# AFE.net
KiCad netlist of a schematic drawn in Altium Designer
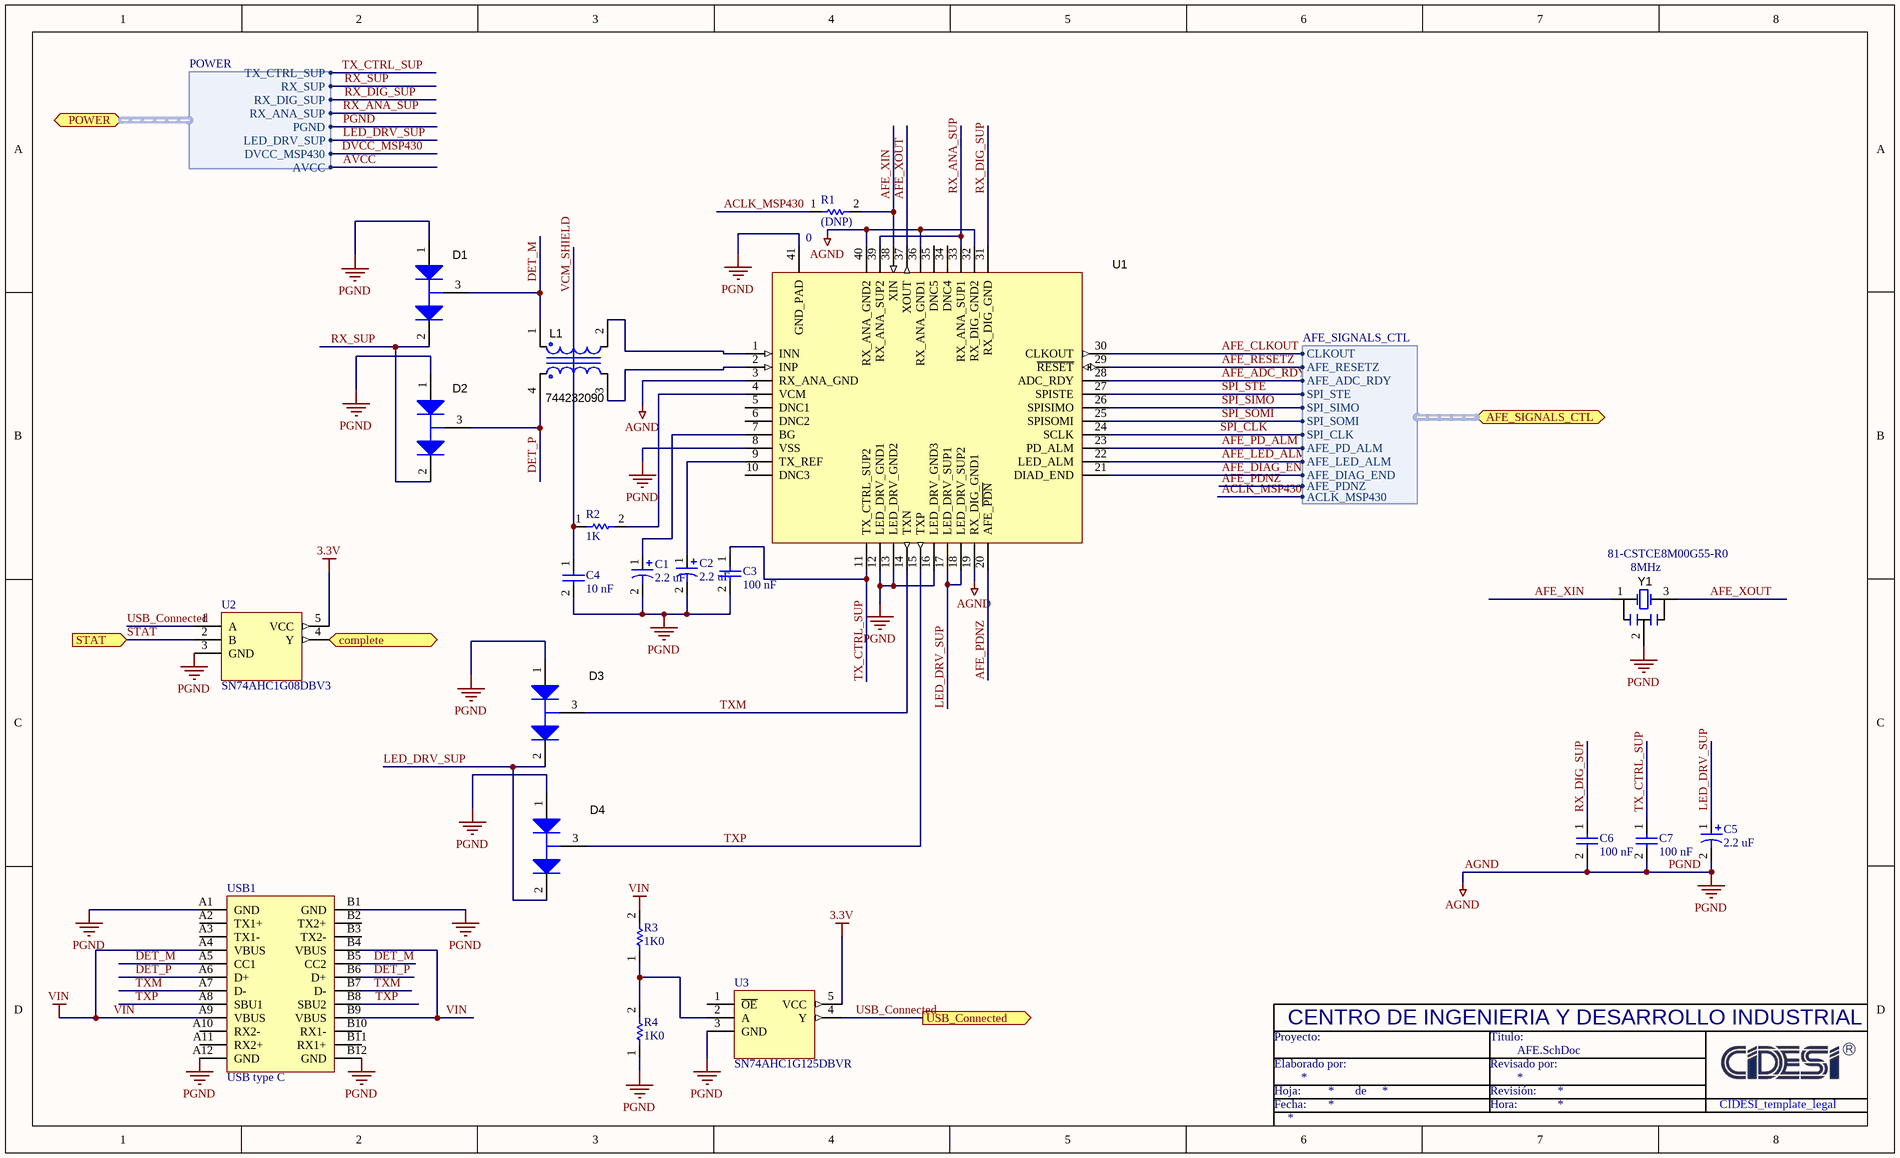
[diagram p0: AFE.SchDoc]

(export (version "E")
  (design (tool "Eeschema 10.0.6"))
  (components
    (comp (ref "C1")
      (value "2.2 uF")
      (footprint "C0603_P")
      (description "NICHICON - F981A225MMA - CAPACITOR TANT, 2.2UF, 10V, SMD 20%")
      (libsource (lib "TarjetaPrincipalV1_4") (part "F981A225MMA"))
    )
    (comp (ref "C2")
      (value "2.2 uF")
      (footprint "C0603_P")
      (description "NICHICON - F981A225MMA - CAPACITOR TANT, 2.2UF, 10V, SMD 20%")
      (libsource (lib "TarjetaPrincipalV1_4") (part "F981A225MMA"))
    )
    (comp (ref "C3")
      (value "100 nF")
      (footprint "C0402")
      (description "TDK - C1005X7R1H104M050BB - CAP CERAMIC, 0.1UF, 50V, X7R, 0402")
      (libsource (lib "TarjetaPrincipalV1_4") (part "C1005X7R1H104M050BB"))
    )
    (comp (ref "C4")
      (value "10 nF")
      (footprint "C0402")
      (description "TDK - C1005X7R1H103K050BB - CAP CERAMIC, 0.01UF, 50V, X7R, 0402")
      (libsource (lib "TarjetaPrincipalV1_4") (part "C1005X7R1H103K050BB"))
    )
    (comp (ref "C5")
      (value "2.2 uF")
      (footprint "C0603_P")
      (description "NICHICON - F981A225MMA - CAPACITOR TANT, 2.2UF, 10V, SMD 20%")
      (libsource (lib "TarjetaPrincipalV1_4") (part "F981A225MMA"))
    )
    (comp (ref "C6")
      (value "100 nF")
      (footprint "C0402")
      (description "TDK - C1005X7R1H104M050BB - CAP CERAMIC, 0.1UF, 50V, X7R, 0402")
      (libsource (lib "TarjetaPrincipalV1_4") (part "C1005X7R1H104M050BB"))
    )
    (comp (ref "C7")
      (value "100 nF")
      (footprint "C0402")
      (description "TDK - C1005X7R1H104M050BB - CAP CERAMIC, 0.1UF, 50V, X7R, 0402")
      (libsource (lib "TarjetaPrincipalV1_4") (part "C1005X7R1H104M050BB"))
    )
    (comp (ref "D1")
      (value "1651159")
      (footprint "SOT-323")
      (description "ON SEMICONDUCTOR - BAV99WT1G - DIODE SMALL SIGNAL, 750MA")
      (fields (field (name "PART NUMBER") "BAV99WT1G") (field (name "MANUFACTURER") "ON SEMICONDUCTOR"))
      (libsource (lib "TarjetaPrincipalV1_4") (part "BAV99WT1G"))
    )
    (comp (ref "D2")
      (value "1651159")
      (footprint "SOT-323")
      (description "ON SEMICONDUCTOR - BAV99WT1G - DIODE SMALL SIGNAL, 750MA")
      (fields (field (name "PART NUMBER") "BAV99WT1G") (field (name "MANUFACTURER") "ON SEMICONDUCTOR"))
      (libsource (lib "TarjetaPrincipalV1_4") (part "BAV99WT1G"))
    )
    (comp (ref "D3")
      (value "1651159")
      (footprint "SOT-323")
      (description "ON SEMICONDUCTOR - BAV99WT1G - DIODE SMALL SIGNAL, 750MA")
      (fields (field (name "PART NUMBER") "BAV99WT1G") (field (name "MANUFACTURER") "ON SEMICONDUCTOR"))
      (libsource (lib "TarjetaPrincipalV1_4") (part "BAV99WT1G"))
    )
    (comp (ref "D4")
      (value "1651159")
      (footprint "SOT-323")
      (description "ON SEMICONDUCTOR - BAV99WT1G - DIODE SMALL SIGNAL, 750MA")
      (fields (field (name "PART NUMBER") "BAV99WT1G") (field (name "MANUFACTURER") "ON SEMICONDUCTOR"))
      (libsource (lib "TarjetaPrincipalV1_4") (part "BAV99WT1G"))
    )
    (comp (ref "L1")
      (value "744232090")
      (footprint "IND_1206-4P")
      (description "WURTH ELEKTRONIK - 744232090 - FILTER, COMMON, EMI, 0.37A")
      (libsource (lib "TarjetaPrincipalV1_4") (part "DLW31SN900SQ2L"))
    )
    (comp (ref "R1")
      (value "(DNP)")
      (footprint "0201")
      (description "VISHAY DALE - CRCW02010000Z0ED - RESISTOR, CHIP, JUMPER, ZERO OHM, 50mW, FULL REEL")
      (fields (field (name "ALTIUM_VALUE") "0"))
      (libsource (lib "TarjetaPrincipalV1_4") (part "CRCW02010000Z0ED"))
    )
    (comp (ref "R2")
      (value "1K")
      (footprint "0201")
      (description "VISHAY DALE - CRCW02011K00FNED - RESISTOR, THICK FILM CHIP, 1KOHM 50mW, 1%, FULL REEL")
      (libsource (lib "TarjetaPrincipalV1_4") (part "CRCW02011K00FNED"))
    )
    (comp (ref "R3")
      (value "CRCW04021K00FKEDC")
      (footprint "R-0402")
      (description "Resistor")
      (fields
        (field (name "MANUFACTURER") "Vishay / Dale")
        (field (name "TOLERANCE") "1 %")
        (field (name "RESISTANCE") "1K0")
      )
      (libsource (lib "TarjetaPrincipalV1_4") (part "CRCW04021K00FKEDC"))
    )
    (comp (ref "R4")
      (value "CRCW04021K00FKEDC")
      (footprint "R-0402")
      (description "Resistor")
      (fields
        (field (name "MANUFACTURER") "Vishay / Dale")
        (field (name "TOLERANCE") "1 %")
        (field (name "RESISTANCE") "1K0")
      )
      (libsource (lib "TarjetaPrincipalV1_4") (part "CRCW04021K00FKEDC"))
    )
    (comp (ref "U1")
      (value "~")
      (footprint "QFN-40[RHA-42P]")
      (description "IC, INTEGRATED ANALOG FRONT-END FOR HEART RATE MONITORS AND LOW-COST PULSE OXIMETERS, QFN-40")
      (fields (field (name "PART NUMBER") "AFE4400") (field (name "MANUFACTURER") "TEXAS INSTRUMENTS"))
      (libsource (lib "TarjetaPrincipalV1_4") (part "AFE4400"))
    )
    (comp (ref "U2")
      (value "~")
      (footprint "SOT23-5")
      (description "AND GATE")
      (fields
        (field (name "MANUFACTURER") "Texas Instruments")
        (field (name "MANUFACTURER PART NUMBER") "SN74AHC1G08DBV3")
      )
      (libsource (lib "TarjetaPrincipalV1_4") (part "SN74AHC1G08DBV3"))
    )
    (comp (ref "U3")
      (value "~")
      (footprint "SOT23-5")
      (description "BUFFER")
      (fields
        (field (name "MANUFACTURER") "Texas Instruments")
        (field (name "MANUFACTURER PART NUMBER") "SN74AHC1G125DBVR")
      )
      (libsource (lib "TarjetaPrincipalV1_4") (part "SN74AHC1G125DBVR"))
    )
    (comp (ref "USB1")
      (value "USB type C")
      (footprint "USB C")
      (libsource (lib "TarjetaPrincipalV1_4") (part "USB C"))
    )
    (comp (ref "Y1")
      (value "8MHz")
      (footprint "RESONATOR-1.3X3.2-MURATA")
      (description "CRYSTAL, PIEZO CERAMIC RESONATOR, 8.00 MHz, SMD, 0.5%, 33pF, SMD")
      (fields
        (field (name "MANUFACTURER") "MURATA")
        (field (name "PART NUMBER") "CSTCE8M00G55-R0")
        (field (name "SUPPLIER PART NUMBER 1") "81-CSTCE8M00G55-R0")
      )
      (libsource (lib "TarjetaPrincipalV1_4") (part "CSTCE8M00G55-R0"))
    )
  )
  (nets
    (net (code "3") (name "/ACLK_MSP430") (class "Default")
      (node (ref "R1") (pin "1") (pinfunction "1_1") (pintype "passive"))
    )
    (net (code "4") (name "/AFE_ADC_RDY") (class "Default")
      (node (ref "U1") (pin "28") (pinfunction "ADC_RDY_28") (pintype "passive"))
    )
    (net (code "5") (name "/AFE_CLKOUT") (class "Default")
      (node (ref "U1") (pin "30") (pinfunction "CLKOUT_30") (pintype "output"))
    )
    (net (code "6") (name "/AFE_DIAG_END") (class "Default")
      (node (ref "U1") (pin "21") (pinfunction "DIAD_END_21") (pintype "passive"))
    )
    (net (code "7") (name "/AFE_LED_ALM") (class "Default")
      (node (ref "U1") (pin "22") (pinfunction "LED_ALM_22") (pintype "passive"))
    )
    (net (code "8") (name "/AFE_PDNZ") (class "Default")
      (node (ref "U1") (pin "20") (pinfunction "AFE_~{PDN}_20") (pintype "power_in"))
    )
    (net (code "9") (name "/AFE_PD_ALM") (class "Default")
      (node (ref "U1") (pin "23") (pinfunction "PD_ALM_23") (pintype "passive"))
    )
    (net (code "10") (name "/AFE_RESETZ") (class "Default")
      (node (ref "U1") (pin "29") (pinfunction "~{RESET}_29") (pintype "bidirectional"))
    )
    (net (code "11") (name "/AFE_XIN") (class "Default")
      (node (ref "R1") (pin "2") (pinfunction "2_2") (pintype "passive"))
      (node (ref "U1") (pin "38") (pinfunction "XIN_38") (pintype "input"))
      (node (ref "Y1") (pin "1") (pinfunction "1_1") (pintype "passive"))
    )
    (net (code "12") (name "/AFE_XOUT") (class "Default")
      (node (ref "U1") (pin "37") (pinfunction "XOUT_37") (pintype "output"))
      (node (ref "Y1") (pin "3") (pinfunction "3_3") (pintype "passive"))
    )
    (net (code "14") (name "/DET_M") (class "Default")
      (node (ref "D1") (pin "3") (pinfunction "A_C_3") (pintype "passive"))
      (node (ref "L1") (pin "1") (pinfunction "1_1") (pintype "passive"))
      (node (ref "USB1") (pin "A5") (pinfunction "CC1_A5") (pintype "passive"))
      (node (ref "USB1") (pin "B5") (pinfunction "CC2_B5") (pintype "passive"))
    )
    (net (code "15") (name "/DET_P") (class "Default")
      (node (ref "D2") (pin "3") (pinfunction "A_C_3") (pintype "passive"))
      (node (ref "L1") (pin "4") (pinfunction "4_4") (pintype "passive"))
      (node (ref "USB1") (pin "A6") (pinfunction "D+_A6") (pintype "passive"))
      (node (ref "USB1") (pin "B6") (pinfunction "D+_B6") (pintype "passive"))
    )
    (net (code "17") (name "/LED_DRV_SUP") (class "Default")
      (node (ref "C5") (pin "1") (pinfunction "+_1") (pintype "passive"))
      (node (ref "D3") (pin "2") (pinfunction "C_2") (pintype "passive"))
      (node (ref "D4") (pin "2") (pinfunction "C_2") (pintype "passive"))
      (node (ref "U1") (pin "17") (pinfunction "LED_DRV_SUP1_17") (pintype "power_in"))
      (node (ref "U1") (pin "18") (pinfunction "LED_DRV_SUP2_18") (pintype "power_in"))
    )
    (net (code "18") (name "/RX_ANA_SUP") (class "Default")
      (node (ref "U1") (pin "33") (pinfunction "RX_ANA_SUP1_33") (pintype "power_in"))
      (node (ref "U1") (pin "39") (pinfunction "RX_ANA_SUP2_39") (pintype "power_in"))
    )
    (net (code "19") (name "/RX_DIG_SUP") (class "Default")
      (node (ref "C6") (pin "1") (pinfunction "1_1") (pintype "passive"))
      (node (ref "U1") (pin "31") (pinfunction "RX_DIG_GND_31") (pintype "power_in"))
    )
    (net (code "20") (name "/RX_SUP") (class "Default")
      (node (ref "D1") (pin "2") (pinfunction "C_2") (pintype "passive"))
      (node (ref "D2") (pin "2") (pinfunction "C_2") (pintype "passive"))
    )
    (net (code "21") (name "/SPI_CLK") (class "Default")
      (node (ref "U1") (pin "24") (pinfunction "SCLK_24") (pintype "passive"))
    )
    (net (code "22") (name "/SPI_SIMO") (class "Default")
      (node (ref "U1") (pin "26") (pinfunction "SPISIMO_26") (pintype "passive"))
    )
    (net (code "23") (name "/SPI_SOMI") (class "Default")
      (node (ref "U1") (pin "25") (pinfunction "SPISOMI_25") (pintype "passive"))
    )
    (net (code "24") (name "/SPI_STE") (class "Default")
      (node (ref "U1") (pin "27") (pinfunction "SPISTE_27") (pintype "passive"))
    )
    (net (code "25") (name "/STAT") (class "Default")
      (node (ref "U2") (pin "2") (pinfunction "B_2") (pintype "passive"))
    )
    (net (code "26") (name "/TXM") (class "Default")
      (node (ref "D3") (pin "3") (pinfunction "A_C_3") (pintype "passive"))
      (node (ref "U1") (pin "14") (pinfunction "TXN_14") (pintype "output"))
      (node (ref "USB1") (pin "A7") (pinfunction "D-_A7") (pintype "passive"))
      (node (ref "USB1") (pin "B7") (pinfunction "D-_B7") (pintype "passive"))
    )
    (net (code "27") (name "/TXP") (class "Default")
      (node (ref "D4") (pin "3") (pinfunction "A_C_3") (pintype "passive"))
      (node (ref "U1") (pin "15") (pinfunction "TXP_15") (pintype "output"))
      (node (ref "USB1") (pin "A8") (pinfunction "SBU1_A8") (pintype "passive"))
      (node (ref "USB1") (pin "B8") (pinfunction "SBU2_B8") (pintype "passive"))
    )
    (net (code "28") (name "/TX_CTRL_SUP") (class "Default")
      (node (ref "C3") (pin "1") (pinfunction "1_1") (pintype "passive"))
      (node (ref "C7") (pin "1") (pinfunction "1_1") (pintype "passive"))
      (node (ref "U1") (pin "11") (pinfunction "TX_CTRL_SUP2_11") (pintype "power_in"))
    )
    (net (code "29") (name "/USB_Connected") (class "Default")
      (node (ref "U2") (pin "1") (pinfunction "A_1") (pintype "power_in"))
      (node (ref "U3") (pin "4") (pinfunction "Y_4") (pintype "output"))
    )
    (net (code "30") (name "/VCM_SHIELD") (class "Default")
      (node (ref "C4") (pin "1") (pinfunction "1_1") (pintype "passive"))
      (node (ref "R2") (pin "1") (pinfunction "1_1") (pintype "passive"))
    )
    (net (code "31") (name "/complete") (class "Default")
      (node (ref "U2") (pin "4") (pinfunction "Y_4") (pintype "output"))
    )
    (net (code "34") (name "3.3V") (class "Default")
      (node (ref "U2") (pin "5") (pinfunction "VCC_5") (pintype "output"))
      (node (ref "U3") (pin "5") (pinfunction "VCC_5") (pintype "output"))
    )
    (net (code "35") (name "AGND") (class "Default")
      (node (ref "C1") (pin "2") (pinfunction "-_2") (pintype "passive"))
      (node (ref "C2") (pin "2") (pinfunction "-_2") (pintype "passive"))
      (node (ref "C3") (pin "2") (pinfunction "2_2") (pintype "passive"))
      (node (ref "C4") (pin "2") (pinfunction "2_2") (pintype "passive"))
      (node (ref "C5") (pin "2") (pinfunction "-_2") (pintype "passive"))
      (node (ref "C6") (pin "2") (pinfunction "2_2") (pintype "passive"))
      (node (ref "C7") (pin "2") (pinfunction "2_2") (pintype "passive"))
      (node (ref "D1") (pin "1") (pinfunction "A_1") (pintype "passive"))
      (node (ref "D2") (pin "1") (pinfunction "A_1") (pintype "passive"))
      (node (ref "D3") (pin "1") (pinfunction "A_1") (pintype "passive"))
      (node (ref "D4") (pin "1") (pinfunction "A_1") (pintype "passive"))
      (node (ref "R4") (pin "1") (pinfunction "1_1") (pintype "passive"))
      (node (ref "U1") (pin "12") (pinfunction "LED_DRV_GND1_12") (pintype "power_in"))
      (node (ref "U1") (pin "13") (pinfunction "LED_DRV_GND2_13") (pintype "power_in"))
      (node (ref "U1") (pin "16") (pinfunction "LED_DRV_GND3_16") (pintype "power_in"))
      (node (ref "U1") (pin "19") (pinfunction "RX_DIG_GND1_19") (pintype "power_in"))
      (node (ref "U1") (pin "3") (pinfunction "RX_ANA_GND_3") (pintype "power_in"))
      (node (ref "U1") (pin "32") (pinfunction "RX_DIG_GND2_32") (pintype "power_in"))
      (node (ref "U1") (pin "36") (pinfunction "RX_ANA_GND1_36") (pintype "power_in"))
      (node (ref "U1") (pin "40") (pinfunction "RX_ANA_GND2_40") (pintype "power_in"))
      (node (ref "U1") (pin "41") (pinfunction "GND_PAD_41") (pintype "power_in"))
      (node (ref "U1") (pin "8") (pinfunction "VSS_8") (pintype "power_in"))
      (node (ref "U2") (pin "3") (pinfunction "GND_3") (pintype "passive"))
      (node (ref "U3") (pin "3") (pinfunction "GND_3") (pintype "passive"))
      (node (ref "USB1") (pin "A1") (pinfunction "GND_A1") (pintype "passive"))
      (node (ref "USB1") (pin "A12") (pinfunction "GND_A12") (pintype "passive"))
      (node (ref "USB1") (pin "B1") (pinfunction "GND_B1") (pintype "passive"))
      (node (ref "USB1") (pin "B12") (pinfunction "GND_B12") (pintype "passive"))
      (node (ref "Y1") (pin "2") (pinfunction "2_2") (pintype "passive"))
    )
    (net (code "36") (name "Net-(C1-+)") (class "Default")
      (node (ref "C1") (pin "1") (pinfunction "+_1") (pintype "passive"))
      (node (ref "U1") (pin "7") (pinfunction "BG_7") (pintype "passive"))
    )
    (net (code "37") (name "Net-(C2-+)") (class "Default")
      (node (ref "C2") (pin "1") (pinfunction "+_1") (pintype "passive"))
      (node (ref "U1") (pin "9") (pinfunction "TX_REF_9") (pintype "power_in"))
    )
    (net (code "38") (name "Net-(U1-INN)") (class "Default")
      (node (ref "L1") (pin "2") (pinfunction "2_2") (pintype "passive"))
      (node (ref "U1") (pin "1") (pinfunction "INN_1") (pintype "input"))
    )
    (net (code "39") (name "Net-(U1-INP)") (class "Default")
      (node (ref "L1") (pin "3") (pinfunction "3_3") (pintype "passive"))
      (node (ref "U1") (pin "2") (pinfunction "INP_2") (pintype "input"))
    )
    (net (code "40") (name "Net-(U1-VCM)") (class "Default")
      (node (ref "R2") (pin "2") (pinfunction "2_2") (pintype "passive"))
      (node (ref "U1") (pin "4") (pinfunction "VCM_4") (pintype "power_in"))
    )
    (net (code "41") (name "Net-(U3-A)") (class "Default")
      (node (ref "R3") (pin "1") (pinfunction "1_1") (pintype "passive"))
      (node (ref "R4") (pin "2") (pinfunction "2_2") (pintype "passive"))
      (node (ref "U3") (pin "2") (pinfunction "A_2") (pintype "passive"))
    )
    (net (code "42") (name "VIN") (class "Default")
      (node (ref "R3") (pin "2") (pinfunction "2_2") (pintype "passive"))
      (node (ref "USB1") (pin "A4") (pinfunction "VBUS_A4") (pintype "passive"))
      (node (ref "USB1") (pin "A9") (pinfunction "VBUS_A9") (pintype "passive"))
      (node (ref "USB1") (pin "B4") (pinfunction "VBUS_B4") (pintype "passive"))
      (node (ref "USB1") (pin "B9") (pinfunction "VBUS_B9") (pintype "passive"))
    )
    (net (code "43") (name "unconnected-(U1-DNC1-Pad5)") (class "Default")
      (node (ref "U1") (pin "5") (pinfunction "DNC1_5") (pintype "passive"))
    )
    (net (code "44") (name "unconnected-(U1-DNC2-Pad6)") (class "Default")
      (node (ref "U1") (pin "6") (pinfunction "DNC2_6") (pintype "passive"))
    )
    (net (code "45") (name "unconnected-(U1-DNC3-Pad10)") (class "Default")
      (node (ref "U1") (pin "10") (pinfunction "DNC3_10") (pintype "passive"))
    )
    (net (code "46") (name "unconnected-(U1-DNC4-Pad34)") (class "Default")
      (node (ref "U1") (pin "34") (pinfunction "DNC4_34") (pintype "passive"))
    )
    (net (code "47") (name "unconnected-(U1-DNC5-Pad35)") (class "Default")
      (node (ref "U1") (pin "35") (pinfunction "DNC5_35") (pintype "passive"))
    )
    (net (code "48") (name "unconnected-(U3-~{OE}-Pad1)") (class "Default")
      (node (ref "U3") (pin "1") (pinfunction "~{OE}_1") (pintype "power_in"))
    )
    (net (code "49") (name "unconnected-(USB1-RX1+-PadB11)") (class "Default")
      (node (ref "USB1") (pin "B11") (pinfunction "RX1+_B11") (pintype "passive"))
    )
    (net (code "50") (name "unconnected-(USB1-RX1--PadB10)") (class "Default")
      (node (ref "USB1") (pin "B10") (pinfunction "RX1-_B10") (pintype "passive"))
    )
    (net (code "51") (name "unconnected-(USB1-RX2+-PadA11)") (class "Default")
      (node (ref "USB1") (pin "A11") (pinfunction "RX2+_A11") (pintype "passive"))
    )
    (net (code "52") (name "unconnected-(USB1-RX2--PadA10)") (class "Default")
      (node (ref "USB1") (pin "A10") (pinfunction "RX2-_A10") (pintype "passive"))
    )
    (net (code "53") (name "unconnected-(USB1-TX1+-PadA2)") (class "Default")
      (node (ref "USB1") (pin "A2") (pinfunction "TX1+_A2") (pintype "passive"))
    )
    (net (code "54") (name "unconnected-(USB1-TX1--PadA3)") (class "Default")
      (node (ref "USB1") (pin "A3") (pinfunction "TX1-_A3") (pintype "passive"))
    )
    (net (code "55") (name "unconnected-(USB1-TX2+-PadB2)") (class "Default")
      (node (ref "USB1") (pin "B2") (pinfunction "TX2+_B2") (pintype "passive"))
    )
    (net (code "56") (name "unconnected-(USB1-TX2--PadB3)") (class "Default")
      (node (ref "USB1") (pin "B3") (pinfunction "TX2-_B3") (pintype "passive"))
    )
  )
)
